# ADS129x.net
KiCad netlist of a schematic drawn in Altium Designer
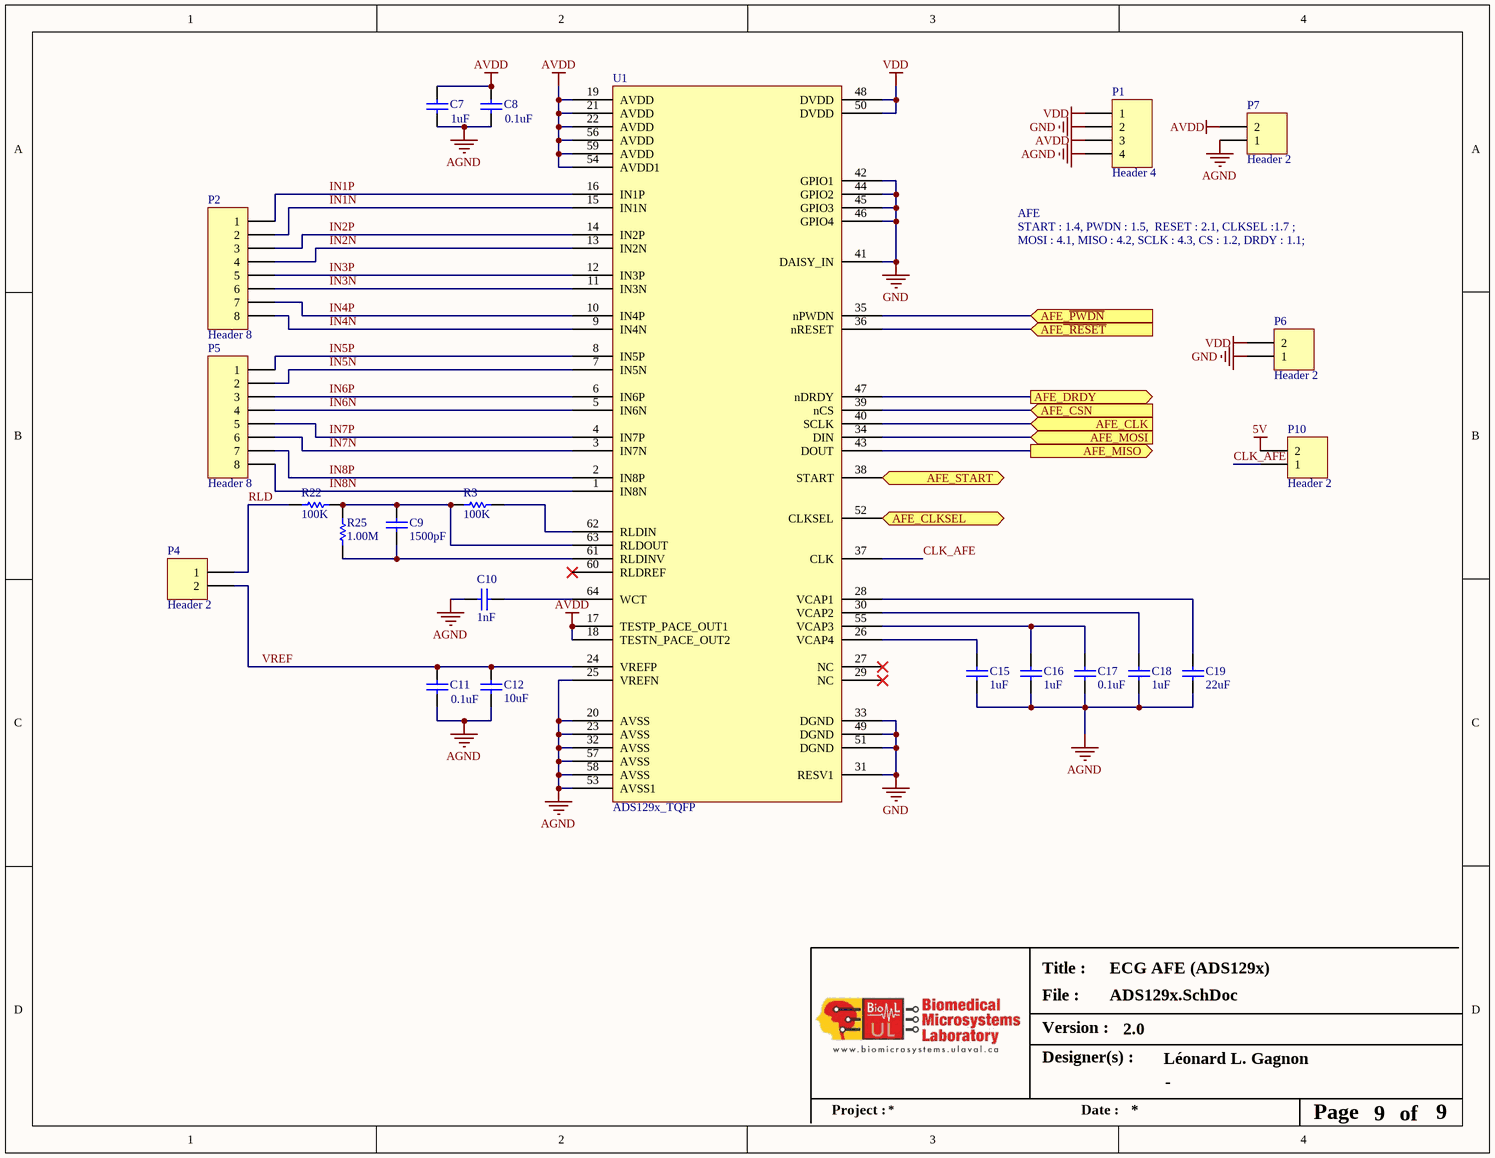
[diagram p0: ADS129x.SchDoc]

(export (version "E")
  (design (tool "Eeschema 10.0.6"))
  (components
    (comp (ref "C7")
      (value "1uF")
      (footprint "0402")
      (description "Capacitor")
      (fields (field (name "Comment") "Cap"))
      (libsource (lib "Miscellaneous Devices") (part "Cap"))
    )
    (comp (ref "C8")
      (value "0.1uF")
      (footprint "0402")
      (description "Capacitor")
      (fields (field (name "Comment") "Cap"))
      (libsource (lib "Miscellaneous Devices") (part "Cap"))
    )
    (comp (ref "C9")
      (value "1500pF")
      (footprint "0402")
      (description "Capacitor")
      (fields (field (name "Comment") "Cap"))
      (libsource (lib "Miscellaneous Devices") (part "Cap"))
    )
    (comp (ref "C10")
      (value "1nF")
      (footprint "0402")
      (description "Capacitor")
      (fields (field (name "Comment") "Cap"))
      (libsource (lib "Miscellaneous Devices") (part "Cap"))
    )
    (comp (ref "C11")
      (value "0.1uF")
      (footprint "0402")
      (description "Capacitor")
      (fields (field (name "Comment") "Cap"))
      (libsource (lib "Miscellaneous Devices") (part "Cap"))
    )
    (comp (ref "C12")
      (value "10uF")
      (footprint "0402")
      (description "Capacitor (Semiconductor SIM Model)")
      (libsource (lib "Miscellaneous Devices") (part "Cap Semi"))
    )
    (comp (ref "C15")
      (value "1uF")
      (footprint "0402")
      (description "Capacitor")
      (fields (field (name "Comment") "Cap"))
      (libsource (lib "Miscellaneous Devices") (part "Cap"))
    )
    (comp (ref "C16")
      (value "1uF")
      (footprint "0402")
      (description "Capacitor")
      (fields (field (name "Comment") "Cap"))
      (libsource (lib "Miscellaneous Devices") (part "Cap"))
    )
    (comp (ref "C17")
      (value "0.1uF")
      (footprint "0402")
      (description "Capacitor")
      (fields (field (name "Comment") "Cap"))
      (libsource (lib "Miscellaneous Devices") (part "Cap"))
    )
    (comp (ref "C18")
      (value "1uF")
      (footprint "0402")
      (description "Capacitor")
      (fields (field (name "Comment") "Cap"))
      (libsource (lib "Miscellaneous Devices") (part "Cap"))
    )
    (comp (ref "C19")
      (value "22uF")
      (footprint "0402")
      (description "Capacitor")
      (fields (field (name "Comment") "Cap"))
      (libsource (lib "Miscellaneous Devices") (part "Cap"))
    )
    (comp (ref "P1")
      (value "Header 4")
      (footprint "HDR1X4")
      (description "Header, 4-Pin")
      (fields (field (name "PUBLISHER") "Altium Limited"))
      (libsource (lib "Miscellaneous Connectors") (part "Header 4"))
    )
    (comp (ref "P2")
      (value "Header 8")
      (footprint "HDR1X8")
      (description "Header, 8-Pin")
      (fields (field (name "PUBLISHER") "Altium Limited"))
      (libsource (lib "Miscellaneous Connectors") (part "Header 8"))
    )
    (comp (ref "P4")
      (value "Header 2")
      (footprint "HDR1X2")
      (description "Header, 2-Pin")
      (fields (field (name "PUBLISHER") "Altium Limited"))
      (libsource (lib "") (part "Header 2_1"))
    )
    (comp (ref "P5")
      (value "Header 8")
      (footprint "HDR1X8")
      (description "Header, 8-Pin")
      (fields (field (name "PUBLISHER") "Altium Limited"))
      (libsource (lib "Miscellaneous Connectors") (part "Header 8"))
    )
    (comp (ref "P6")
      (value "Header 2")
      (footprint "HDR1X2")
      (description "Header, 2-Pin")
      (fields (field (name "PUBLISHER") "Altium Limited"))
      (libsource (lib "Miscellaneous Connectors") (part "Header 2"))
    )
    (comp (ref "P7")
      (value "Header 2")
      (footprint "HDR1X2")
      (description "Header, 2-Pin")
      (fields (field (name "PUBLISHER") "Altium Limited"))
      (libsource (lib "Miscellaneous Connectors") (part "Header 2"))
    )
    (comp (ref "P10")
      (value "Header 2")
      (footprint "HDR1X2")
      (description "Header, 2-Pin")
      (fields (field (name "PUBLISHER") "Altium Limited"))
      (libsource (lib "Miscellaneous Connectors") (part "Header 2"))
    )
    (comp (ref "R3")
      (value "100K")
      (footprint "0402")
      (description "Resistor")
      (fields (field (name "Comment") "Res1"))
      (libsource (lib "Miscellaneous Devices") (part "Res1"))
    )
    (comp (ref "R22")
      (value "100K")
      (footprint "0402")
      (description "Resistor")
      (fields (field (name "Comment") "Res1"))
      (libsource (lib "Miscellaneous Devices") (part "Res1"))
    )
    (comp (ref "R25")
      (value "1.00M")
      (footprint "0402")
      (description "Resistor")
      (fields (field (name "Comment") "Res1"))
      (libsource (lib "Miscellaneous Devices") (part "Res1"))
    )
    (comp (ref "U1")
      (value "ADS129x_TQFP")
      (footprint "PQFP-G64")
      (libsource (lib "ECG_parts") (part "ADS129x_TQFP"))
    )
  )
  (nets
    (net (code "1") (name "/AFE_CLK") (class "Default")
      (node (ref "U1") (pin "40") (pinfunction "SCLK_40") (pintype "passive"))
    )
    (net (code "2") (name "/AFE_CLKSEL") (class "Default")
      (node (ref "U1") (pin "52") (pinfunction "CLKSEL_52") (pintype "passive"))
    )
    (net (code "3") (name "/AFE_CSN") (class "Default")
      (node (ref "U1") (pin "39") (pinfunction "nCS_39") (pintype "passive"))
    )
    (net (code "4") (name "/AFE_DRDY") (class "Default")
      (node (ref "U1") (pin "47") (pinfunction "nDRDY_47") (pintype "passive"))
    )
    (net (code "5") (name "/AFE_MISO") (class "Default")
      (node (ref "U1") (pin "43") (pinfunction "DOUT_43") (pintype "passive"))
    )
    (net (code "6") (name "/AFE_MOSI") (class "Default")
      (node (ref "U1") (pin "34") (pinfunction "DIN_34") (pintype "passive"))
    )
    (net (code "7") (name "/AFE_START") (class "Default")
      (node (ref "U1") (pin "38") (pinfunction "START_38") (pintype "passive"))
    )
    (net (code "8") (name "/AFE_~{PWDN}") (class "Default")
      (node (ref "U1") (pin "35") (pinfunction "nPWDN_35") (pintype "passive"))
    )
    (net (code "9") (name "/AFE~{_RESET}") (class "Default")
      (node (ref "U1") (pin "36") (pinfunction "nRESET_36") (pintype "passive"))
    )
    (net (code "10") (name "/CLK_AFE") (class "Default")
      (node (ref "P10") (pin "1") (pinfunction "1_1") (pintype "passive"))
      (node (ref "U1") (pin "37") (pinfunction "CLK_37") (pintype "passive"))
    )
    (net (code "11") (name "/IN1N") (class "Default")
      (node (ref "P2") (pin "2") (pinfunction "2_2") (pintype "passive"))
      (node (ref "U1") (pin "15") (pinfunction "IN1N_15") (pintype "passive"))
    )
    (net (code "12") (name "/IN1P") (class "Default")
      (node (ref "P2") (pin "1") (pinfunction "1_1") (pintype "passive"))
      (node (ref "U1") (pin "16") (pinfunction "IN1P_16") (pintype "passive"))
    )
    (net (code "13") (name "/IN2N") (class "Default")
      (node (ref "P2") (pin "4") (pinfunction "4_4") (pintype "passive"))
      (node (ref "U1") (pin "13") (pinfunction "IN2N_13") (pintype "passive"))
    )
    (net (code "14") (name "/IN2P") (class "Default")
      (node (ref "P2") (pin "3") (pinfunction "3_3") (pintype "passive"))
      (node (ref "U1") (pin "14") (pinfunction "IN2P_14") (pintype "passive"))
    )
    (net (code "15") (name "/IN3N") (class "Default")
      (node (ref "P2") (pin "6") (pinfunction "6_6") (pintype "passive"))
      (node (ref "U1") (pin "11") (pinfunction "IN3N_11") (pintype "passive"))
    )
    (net (code "16") (name "/IN3P") (class "Default")
      (node (ref "P2") (pin "5") (pinfunction "5_5") (pintype "passive"))
      (node (ref "U1") (pin "12") (pinfunction "IN3P_12") (pintype "passive"))
    )
    (net (code "17") (name "/IN4N") (class "Default")
      (node (ref "P2") (pin "8") (pinfunction "8_8") (pintype "passive"))
      (node (ref "U1") (pin "9") (pinfunction "IN4N_9") (pintype "passive"))
    )
    (net (code "18") (name "/IN4P") (class "Default")
      (node (ref "P2") (pin "7") (pinfunction "7_7") (pintype "passive"))
      (node (ref "U1") (pin "10") (pinfunction "IN4P_10") (pintype "passive"))
    )
    (net (code "19") (name "/IN5N") (class "Default")
      (node (ref "P5") (pin "2") (pinfunction "2_2") (pintype "passive"))
      (node (ref "U1") (pin "7") (pinfunction "IN5N_7") (pintype "passive"))
    )
    (net (code "20") (name "/IN5P") (class "Default")
      (node (ref "P5") (pin "1") (pinfunction "1_1") (pintype "passive"))
      (node (ref "U1") (pin "8") (pinfunction "IN5P_8") (pintype "passive"))
    )
    (net (code "21") (name "/IN6N") (class "Default")
      (node (ref "P5") (pin "4") (pinfunction "4_4") (pintype "passive"))
      (node (ref "U1") (pin "5") (pinfunction "IN6N_5") (pintype "passive"))
    )
    (net (code "22") (name "/IN6P") (class "Default")
      (node (ref "P5") (pin "3") (pinfunction "3_3") (pintype "passive"))
      (node (ref "U1") (pin "6") (pinfunction "IN6P_6") (pintype "passive"))
    )
    (net (code "23") (name "/IN7N") (class "Default")
      (node (ref "P5") (pin "6") (pinfunction "6_6") (pintype "passive"))
      (node (ref "U1") (pin "3") (pinfunction "IN7N_3") (pintype "passive"))
    )
    (net (code "24") (name "/IN7P") (class "Default")
      (node (ref "P5") (pin "5") (pinfunction "5_5") (pintype "passive"))
      (node (ref "U1") (pin "4") (pinfunction "IN7P_4") (pintype "passive"))
    )
    (net (code "25") (name "/IN8N") (class "Default")
      (node (ref "P5") (pin "8") (pinfunction "8_8") (pintype "passive"))
      (node (ref "U1") (pin "1") (pinfunction "IN8N_1") (pintype "passive"))
    )
    (net (code "26") (name "/IN8P") (class "Default")
      (node (ref "P5") (pin "7") (pinfunction "7_7") (pintype "passive"))
      (node (ref "U1") (pin "2") (pinfunction "IN8P_2") (pintype "passive"))
    )
    (net (code "27") (name "/RLD") (class "Default")
      (node (ref "P4") (pin "1") (pinfunction "1_1") (pintype "passive"))
      (node (ref "R22") (pin "2") (pinfunction "2_2") (pintype "passive"))
    )
    (net (code "28") (name "/VREF") (class "Default")
      (node (ref "C11") (pin "2") (pinfunction "2_2") (pintype "passive"))
      (node (ref "C12") (pin "2") (pinfunction "2_2") (pintype "passive"))
      (node (ref "P4") (pin "2") (pinfunction "2_2") (pintype "passive"))
      (node (ref "U1") (pin "24") (pinfunction "VREFP_24") (pintype "passive"))
    )
    (net (code "29") (name "5V") (class "Default")
      (node (ref "P10") (pin "2") (pinfunction "2_2") (pintype "passive"))
    )
    (net (code "30") (name "AGND") (class "Default")
      (node (ref "C10") (pin "2") (pinfunction "2_2") (pintype "passive"))
      (node (ref "C11") (pin "1") (pinfunction "1_1") (pintype "passive"))
      (node (ref "C12") (pin "1") (pinfunction "1_1") (pintype "passive"))
      (node (ref "C15") (pin "2") (pinfunction "2_2") (pintype "passive"))
      (node (ref "C16") (pin "2") (pinfunction "2_2") (pintype "passive"))
      (node (ref "C17") (pin "2") (pinfunction "2_2") (pintype "passive"))
      (node (ref "C18") (pin "2") (pinfunction "2_2") (pintype "passive"))
      (node (ref "C19") (pin "2") (pinfunction "2_2") (pintype "passive"))
      (node (ref "C7") (pin "1") (pinfunction "1_1") (pintype "passive"))
      (node (ref "C8") (pin "1") (pinfunction "1_1") (pintype "passive"))
      (node (ref "P1") (pin "4") (pinfunction "4_4") (pintype "passive"))
      (node (ref "P7") (pin "1") (pinfunction "1_1") (pintype "passive"))
      (node (ref "U1") (pin "20") (pinfunction "AVSS_20") (pintype "passive"))
      (node (ref "U1") (pin "23") (pinfunction "AVSS_23") (pintype "passive"))
      (node (ref "U1") (pin "25") (pinfunction "VREFN_25") (pintype "passive"))
      (node (ref "U1") (pin "32") (pinfunction "AVSS_32") (pintype "passive"))
      (node (ref "U1") (pin "53") (pinfunction "AVSS1_53") (pintype "passive"))
      (node (ref "U1") (pin "57") (pinfunction "AVSS_57") (pintype "passive"))
      (node (ref "U1") (pin "58") (pinfunction "AVSS_58") (pintype "passive"))
    )
    (net (code "31") (name "AVDD") (class "Default")
      (node (ref "C7") (pin "2") (pinfunction "2_2") (pintype "passive"))
      (node (ref "C8") (pin "2") (pinfunction "2_2") (pintype "passive"))
      (node (ref "P1") (pin "3") (pinfunction "3_3") (pintype "passive"))
      (node (ref "P7") (pin "2") (pinfunction "2_2") (pintype "passive"))
      (node (ref "U1") (pin "17") (pinfunction "TESTP_PACE_OUT1_17") (pintype "passive"))
      (node (ref "U1") (pin "18") (pinfunction "TESTN_PACE_OUT2_18") (pintype "passive"))
      (node (ref "U1") (pin "19") (pinfunction "AVDD_19") (pintype "passive"))
      (node (ref "U1") (pin "21") (pinfunction "AVDD_21") (pintype "passive"))
      (node (ref "U1") (pin "22") (pinfunction "AVDD_22") (pintype "passive"))
      (node (ref "U1") (pin "54") (pinfunction "AVDD1_54") (pintype "passive"))
      (node (ref "U1") (pin "56") (pinfunction "AVDD_56") (pintype "passive"))
      (node (ref "U1") (pin "59") (pinfunction "AVDD_59") (pintype "passive"))
    )
    (net (code "32") (name "GND") (class "Default")
      (node (ref "P1") (pin "2") (pinfunction "2_2") (pintype "passive"))
      (node (ref "P6") (pin "1") (pinfunction "1_1") (pintype "passive"))
      (node (ref "U1") (pin "31") (pinfunction "RESV1_31") (pintype "passive"))
      (node (ref "U1") (pin "33") (pinfunction "DGND_33") (pintype "passive"))
      (node (ref "U1") (pin "41") (pinfunction "DAISY_IN_41") (pintype "passive"))
      (node (ref "U1") (pin "42") (pinfunction "GPIO1_42") (pintype "passive"))
      (node (ref "U1") (pin "44") (pinfunction "GPIO2_44") (pintype "passive"))
      (node (ref "U1") (pin "45") (pinfunction "GPIO3_45") (pintype "passive"))
      (node (ref "U1") (pin "46") (pinfunction "GPIO4_46") (pintype "passive"))
      (node (ref "U1") (pin "49") (pinfunction "DGND_49") (pintype "passive"))
      (node (ref "U1") (pin "51") (pinfunction "DGND_51") (pintype "passive"))
    )
    (net (code "33") (name "Net-(U1-RLDIN)") (class "Default")
      (node (ref "R3") (pin "1") (pinfunction "1_1") (pintype "passive"))
      (node (ref "U1") (pin "62") (pinfunction "RLDIN_62") (pintype "passive"))
    )
    (net (code "34") (name "Net-(U1-RLDINV)") (class "Default")
      (node (ref "C9") (pin "1") (pinfunction "1_1") (pintype "passive"))
      (node (ref "R25") (pin "2") (pinfunction "2_2") (pintype "passive"))
      (node (ref "U1") (pin "61") (pinfunction "RLDINV_61") (pintype "passive"))
    )
    (net (code "35") (name "Net-(U1-RLDOUT)") (class "Default")
      (node (ref "C9") (pin "2") (pinfunction "2_2") (pintype "passive"))
      (node (ref "R22") (pin "1") (pinfunction "1_1") (pintype "passive"))
      (node (ref "R25") (pin "1") (pinfunction "1_1") (pintype "passive"))
      (node (ref "R3") (pin "2") (pinfunction "2_2") (pintype "passive"))
      (node (ref "U1") (pin "63") (pinfunction "RLDOUT_63") (pintype "passive"))
    )
    (net (code "36") (name "Net-(U1-VCAP1)") (class "Default")
      (node (ref "C19") (pin "1") (pinfunction "1_1") (pintype "passive"))
      (node (ref "U1") (pin "28") (pinfunction "VCAP1_28") (pintype "passive"))
    )
    (net (code "37") (name "Net-(U1-VCAP2)") (class "Default")
      (node (ref "C18") (pin "1") (pinfunction "1_1") (pintype "passive"))
      (node (ref "U1") (pin "30") (pinfunction "VCAP2_30") (pintype "passive"))
    )
    (net (code "38") (name "Net-(U1-VCAP3)") (class "Default")
      (node (ref "C16") (pin "1") (pinfunction "1_1") (pintype "passive"))
      (node (ref "C17") (pin "1") (pinfunction "1_1") (pintype "passive"))
      (node (ref "U1") (pin "55") (pinfunction "VCAP3_55") (pintype "passive"))
    )
    (net (code "39") (name "Net-(U1-VCAP4)") (class "Default")
      (node (ref "C15") (pin "1") (pinfunction "1_1") (pintype "passive"))
      (node (ref "U1") (pin "26") (pinfunction "VCAP4_26") (pintype "passive"))
    )
    (net (code "40") (name "Net-(U1-WCT)") (class "Default")
      (node (ref "C10") (pin "1") (pinfunction "1_1") (pintype "passive"))
      (node (ref "U1") (pin "64") (pinfunction "WCT_64") (pintype "passive"))
    )
    (net (code "41") (name "VDD") (class "Default")
      (node (ref "P1") (pin "1") (pinfunction "1_1") (pintype "passive"))
      (node (ref "P6") (pin "2") (pinfunction "2_2") (pintype "passive"))
      (node (ref "U1") (pin "48") (pinfunction "DVDD_48") (pintype "passive"))
      (node (ref "U1") (pin "50") (pinfunction "DVDD_50") (pintype "passive"))
    )
    (net (code "42") (name "unconnected-(U1-NC-Pad27)") (class "Default")
      (node (ref "U1") (pin "27") (pinfunction "NC_27") (pintype "passive+no_connect"))
    )
    (net (code "43") (name "unconnected-(U1-NC-Pad29)") (class "Default")
      (node (ref "U1") (pin "29") (pinfunction "NC_29") (pintype "passive+no_connect"))
    )
    (net (code "44") (name "unconnected-(U1-RLDREF-Pad60)") (class "Default")
      (node (ref "U1") (pin "60") (pinfunction "RLDREF_60") (pintype "passive+no_connect"))
    )
  )
)
